# U2FHIDDevice_0.net
KiCad netlist of a schematic drawn in EAGLE
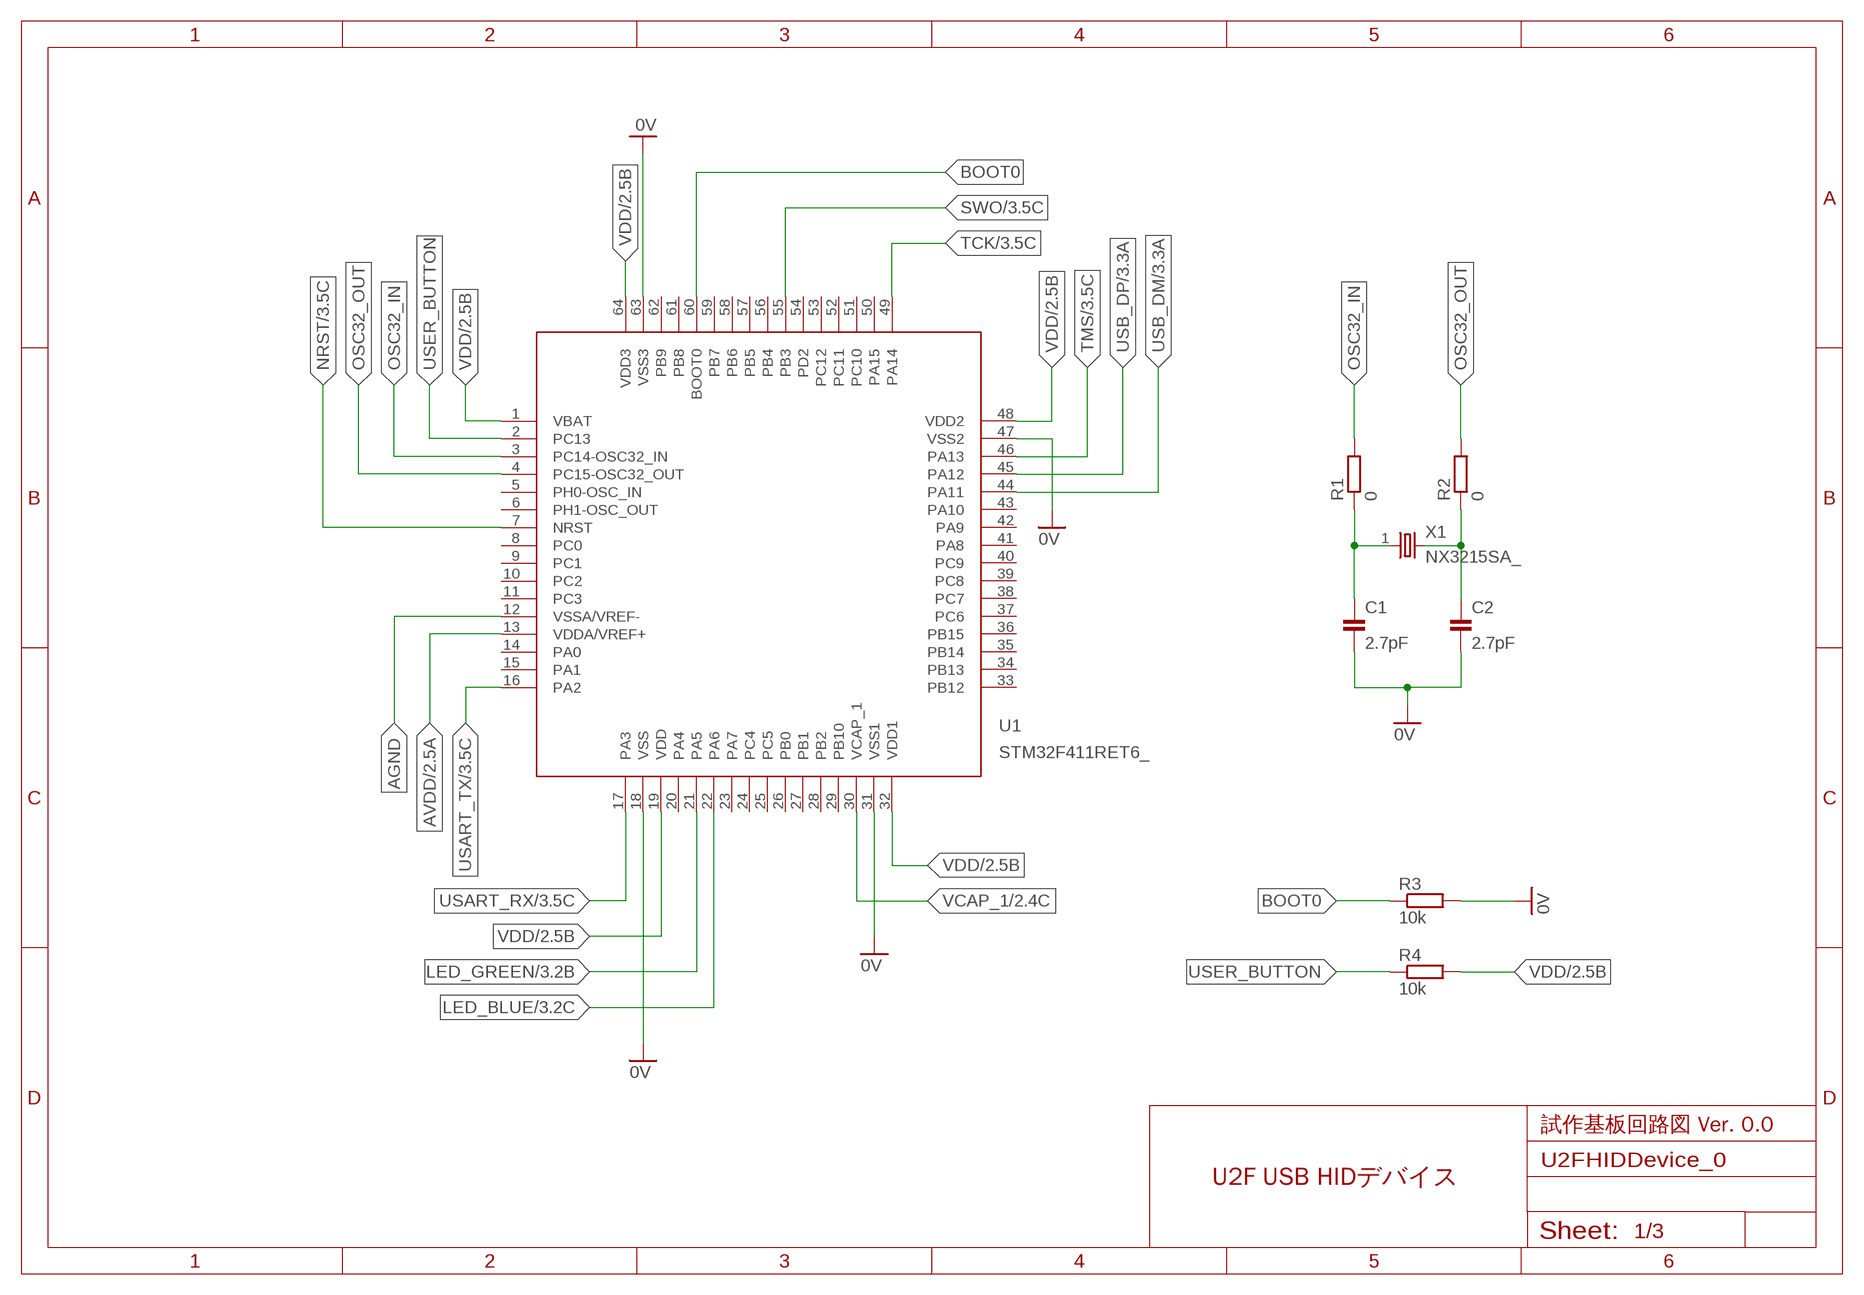
[diagram p0: schematic, sheet 1]
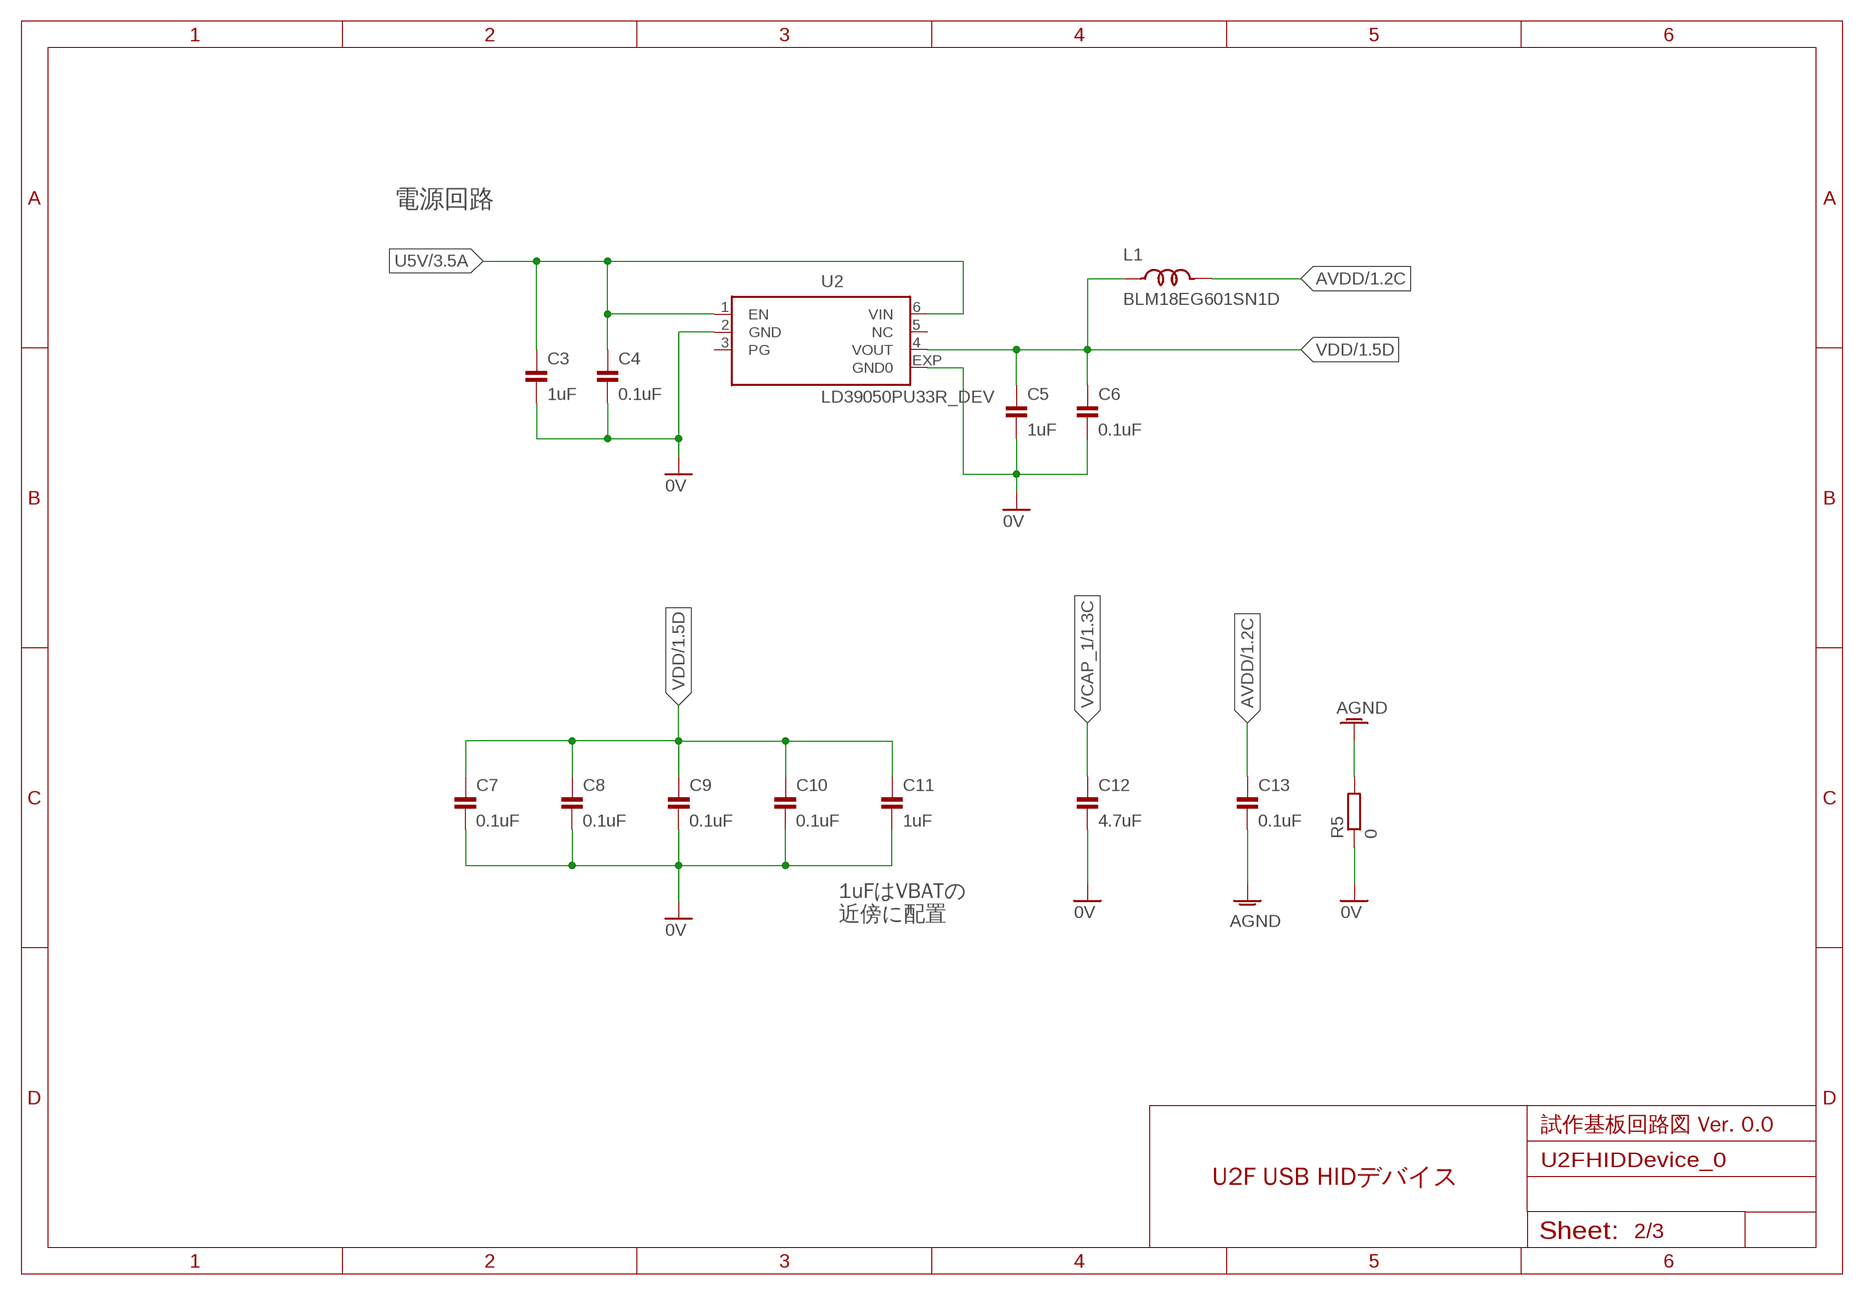
[diagram p1: schematic, sheet 2]
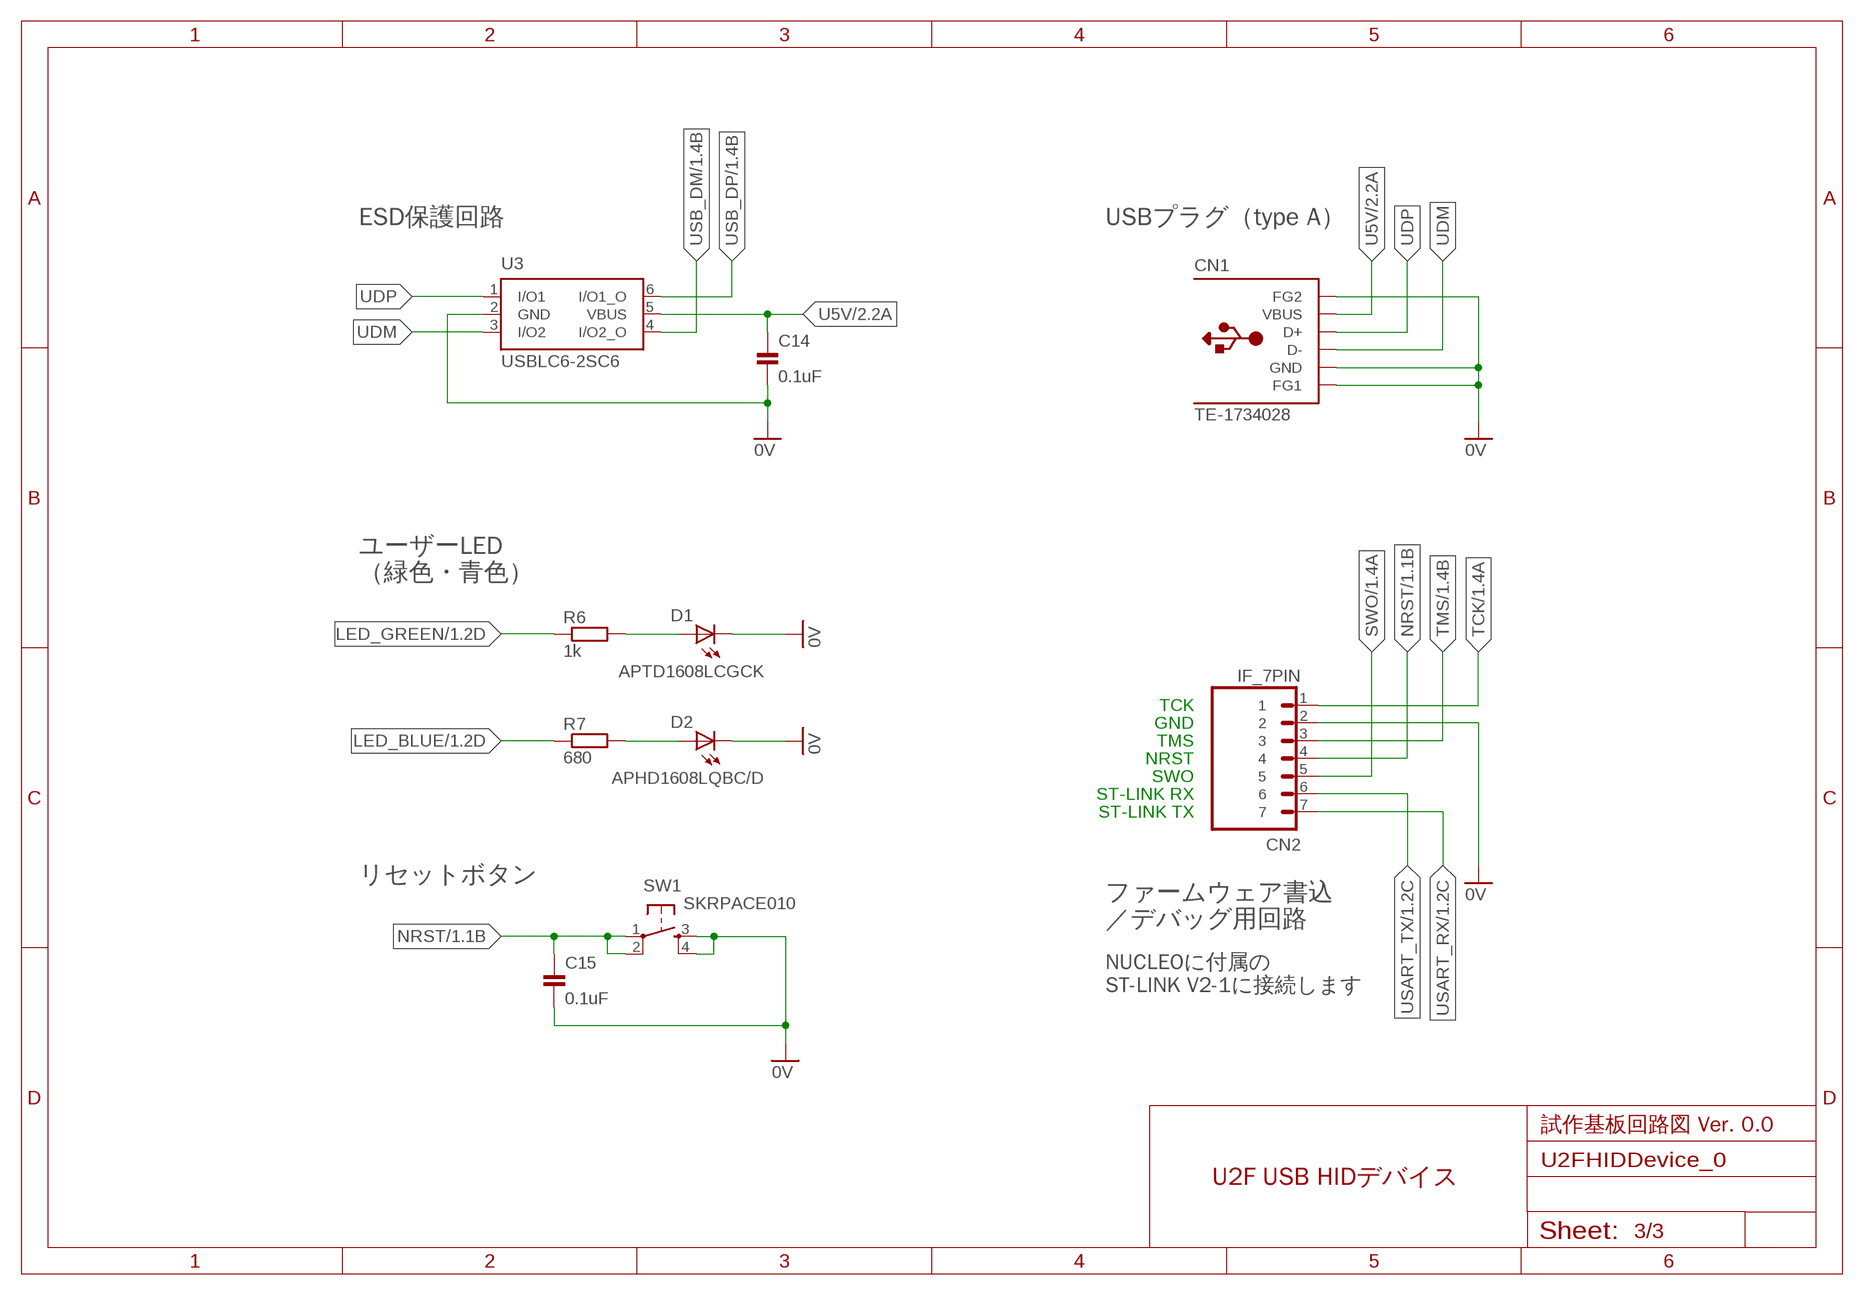
[diagram p2: schematic, sheet 3]

(export (version "E")
  (design (tool "Eeschema 10.0.6"))
  (components
    (comp (ref "C14")
      (value "0.1uF")
      (footprint "eagle-import:C0603K")
      (libsource (lib "eagle-import") (part "CAP_0603"))
    )
    (comp (ref "C15")
      (value "0.1uF")
      (footprint "eagle-import:C0603K")
      (libsource (lib "eagle-import") (part "CAP_0603"))
    )
    (comp (ref "CN1")
      (value "TE-1734028")
      (footprint "eagle-import:TE-1734028")
      (libsource (lib "eagle-import") (part "TE-1734028"))
    )
    (comp (ref "CN2")
      (value "IF_7PIN")
      (footprint "eagle-import:HEADER_7PIN")
      (libsource (lib "eagle-import") (part "IF_7PIN"))
    )
    (comp (ref "D1")
      (value "APTD1608LCGCK")
      (footprint "eagle-import:CHIPLED_0603")
      (libsource (lib "eagle-import") (part "APTD1608LCGCK"))
    )
    (comp (ref "D2")
      (value "APHD1608LQBC/D")
      (footprint "eagle-import:CHIPLED_0603")
      (libsource (lib "eagle-import") (part "APHD1608LQBC/D"))
    )
    (comp (ref "R6")
      (value "1k")
      (footprint "eagle-import:R0603")
      (libsource (lib "eagle-import") (part "RESISTOR_0603"))
    )
    (comp (ref "R7")
      (value "680")
      (footprint "eagle-import:R0603")
      (libsource (lib "eagle-import") (part "RESISTOR_0603"))
    )
    (comp (ref "SW1")
      (value "SKRPACE010")
      (footprint "eagle-import:SKRPACE010")
      (libsource (lib "eagle-import") (part "SKRPACE010"))
    )
    (comp (ref "U3")
      (value "USBLC6-2SC6")
      (footprint "eagle-import:SOT23-6L")
      (libsource (lib "eagle-import") (part "USBLC6-2SC6"))
    )
    (comp (ref "C3")
      (value "1uF")
      (footprint "eagle-import:C0603K")
      (libsource (lib "eagle-import") (part "CAP_0603"))
    )
    (comp (ref "C4")
      (value "0.1uF")
      (footprint "eagle-import:C0603K")
      (libsource (lib "eagle-import") (part "CAP_0603"))
    )
    (comp (ref "C5")
      (value "1uF")
      (footprint "eagle-import:C0603K")
      (libsource (lib "eagle-import") (part "CAP_0603"))
    )
    (comp (ref "C6")
      (value "0.1uF")
      (footprint "eagle-import:C0603K")
      (libsource (lib "eagle-import") (part "CAP_0603"))
    )
    (comp (ref "C7")
      (value "0.1uF")
      (footprint "eagle-import:C0603K")
      (libsource (lib "eagle-import") (part "CAP_0603"))
    )
    (comp (ref "C8")
      (value "0.1uF")
      (footprint "eagle-import:C0603K")
      (libsource (lib "eagle-import") (part "CAP_0603"))
    )
    (comp (ref "C9")
      (value "0.1uF")
      (footprint "eagle-import:C0603K")
      (libsource (lib "eagle-import") (part "CAP_0603"))
    )
    (comp (ref "C10")
      (value "0.1uF")
      (footprint "eagle-import:C0603K")
      (libsource (lib "eagle-import") (part "CAP_0603"))
    )
    (comp (ref "C11")
      (value "1uF")
      (footprint "eagle-import:C0603K")
      (libsource (lib "eagle-import") (part "CAP_0603"))
    )
    (comp (ref "C12")
      (value "4.7uF")
      (footprint "eagle-import:C1206")
      (libsource (lib "eagle-import") (part "CAP_1206"))
    )
    (comp (ref "C13")
      (value "0.1uF")
      (footprint "eagle-import:C0603K")
      (libsource (lib "eagle-import") (part "CAP_0603"))
    )
    (comp (ref "L1")
      (value "BLM18EG601SN1D")
      (footprint "eagle-import:R0603")
      (libsource (lib "eagle-import") (part "BLM18EG601SN1D"))
    )
    (comp (ref "R5")
      (value "0")
      (footprint "eagle-import:R0603")
      (libsource (lib "eagle-import") (part "RESISTOR_0603"))
    )
    (comp (ref "U2")
      (value "LD39050PU33R_DEV")
      (footprint "eagle-import:DFN6-3X3_DEV")
      (libsource (lib "eagle-import") (part "LD39050PU33R_DEV"))
    )
    (comp (ref "C1")
      (value "2.7pF")
      (footprint "eagle-import:C0603K")
      (libsource (lib "eagle-import") (part "CAP_0603"))
    )
    (comp (ref "C2")
      (value "2.7pF")
      (footprint "eagle-import:C0603K")
      (libsource (lib "eagle-import") (part "CAP_0603"))
    )
    (comp (ref "R1")
      (value "0")
      (footprint "eagle-import:R0603")
      (libsource (lib "eagle-import") (part "RESISTOR_0603"))
    )
    (comp (ref "R2")
      (value "0")
      (footprint "eagle-import:R0603")
      (libsource (lib "eagle-import") (part "RESISTOR_0603"))
    )
    (comp (ref "R3")
      (value "10k")
      (footprint "eagle-import:R0603")
      (libsource (lib "eagle-import") (part "RESISTOR_0603"))
    )
    (comp (ref "R4")
      (value "10k")
      (footprint "eagle-import:R0603")
      (libsource (lib "eagle-import") (part "RESISTOR_0603"))
    )
    (comp (ref "U1")
      (value "STM32F411RET6_")
      (footprint "eagle-import:LQFP64-10X10_DEV")
      (libsource (lib "eagle-import") (part "STM32F411RET6_"))
    )
    (comp (ref "X1")
      (value "NX3215SA_")
      (footprint "eagle-import:NX3215_DEV")
      (libsource (lib "eagle-import") (part "NX3215SA_"))
    )
  )
  (nets
    (net (code "1") (name "0V") (class "Default")
      (node (ref "C1") (pin "2") (pinfunction "2_2") (pintype "passive"))
      (node (ref "C10") (pin "2") (pinfunction "2_2") (pintype "passive"))
      (node (ref "C11") (pin "2") (pinfunction "2_2") (pintype "passive"))
      (node (ref "C12") (pin "2") (pinfunction "2_2") (pintype "passive"))
      (node (ref "C14") (pin "2") (pinfunction "2_2") (pintype "passive"))
      (node (ref "C15") (pin "2") (pinfunction "2_2") (pintype "passive"))
      (node (ref "C2") (pin "2") (pinfunction "2_2") (pintype "passive"))
      (node (ref "C3") (pin "2") (pinfunction "2_2") (pintype "passive"))
      (node (ref "C4") (pin "2") (pinfunction "2_2") (pintype "passive"))
      (node (ref "C5") (pin "2") (pinfunction "2_2") (pintype "passive"))
      (node (ref "C6") (pin "2") (pinfunction "2_2") (pintype "passive"))
      (node (ref "C7") (pin "2") (pinfunction "2_2") (pintype "passive"))
      (node (ref "C8") (pin "2") (pinfunction "2_2") (pintype "passive"))
      (node (ref "C9") (pin "2") (pinfunction "2_2") (pintype "passive"))
      (node (ref "CN1") (pin "FG1") (pinfunction "FG1_FG1") (pintype "passive"))
      (node (ref "CN1") (pin "FG2") (pinfunction "FG2_FG2") (pintype "passive"))
      (node (ref "CN1") (pin "P$4") (pinfunction "GND_P$4") (pintype "passive"))
      (node (ref "CN2") (pin "2") (pinfunction "2_2") (pintype "passive"))
      (node (ref "D1") (pin "C") (pinfunction "C_C") (pintype "passive"))
      (node (ref "D2") (pin "C") (pinfunction "C_C") (pintype "passive"))
      (node (ref "R3") (pin "2") (pinfunction "2_2") (pintype "passive"))
      (node (ref "R5") (pin "1") (pinfunction "1_1") (pintype "passive"))
      (node (ref "SW1") (pin "3") (pinfunction "S_3") (pintype "passive"))
      (node (ref "SW1") (pin "4") (pinfunction "S1_4") (pintype "passive"))
      (node (ref "U1") (pin "18") (pinfunction "VSS_18") (pintype "passive"))
      (node (ref "U1") (pin "31") (pinfunction "VSS1_31") (pintype "passive"))
      (node (ref "U1") (pin "47") (pinfunction "VSS2_47") (pintype "passive"))
      (node (ref "U1") (pin "63") (pinfunction "VSS3_63") (pintype "passive"))
      (node (ref "U2") (pin "2") (pinfunction "GND_2") (pintype "passive"))
      (node (ref "U2") (pin "EXP") (pinfunction "GND0_EXP") (pintype "passive"))
      (node (ref "U3") (pin "2") (pinfunction "GND_2") (pintype "passive"))
    )
    (net (code "2") (name "AGND") (class "Default")
      (node (ref "C13") (pin "2") (pinfunction "2_2") (pintype "passive"))
      (node (ref "R5") (pin "2") (pinfunction "2_2") (pintype "passive"))
      (node (ref "U1") (pin "12") (pinfunction "VSSA/VREF-_12") (pintype "passive"))
    )
    (net (code "3") (name "AVDD") (class "Default")
      (node (ref "C13") (pin "1") (pinfunction "1_1") (pintype "passive"))
      (node (ref "L1") (pin "2") (pinfunction "2_2") (pintype "passive"))
      (node (ref "U1") (pin "13") (pinfunction "VDDA/VREF+_13") (pintype "passive"))
    )
    (net (code "4") (name "BOOT0") (class "Default")
      (node (ref "R3") (pin "1") (pinfunction "1_1") (pintype "passive"))
      (node (ref "U1") (pin "60") (pinfunction "BOOT0_60") (pintype "bidirectional"))
    )
    (net (code "5") (name "LED_BLUE") (class "Default")
      (node (ref "R7") (pin "1") (pinfunction "1_1") (pintype "passive"))
      (node (ref "U1") (pin "22") (pinfunction "PA6_22") (pintype "bidirectional"))
    )
    (net (code "6") (name "LED_GREEN") (class "Default")
      (node (ref "R6") (pin "1") (pinfunction "1_1") (pintype "passive"))
      (node (ref "U1") (pin "21") (pinfunction "PA5_21") (pintype "bidirectional"))
    )
    (net (code "7") (name "NRST") (class "Default")
      (node (ref "C15") (pin "1") (pinfunction "1_1") (pintype "passive"))
      (node (ref "CN2") (pin "4") (pinfunction "4_4") (pintype "passive"))
      (node (ref "SW1") (pin "1") (pinfunction "P_1") (pintype "passive"))
      (node (ref "SW1") (pin "2") (pinfunction "P1_2") (pintype "passive"))
      (node (ref "U1") (pin "7") (pinfunction "NRST_7") (pintype "bidirectional"))
    )
    (net (code "8") (name "Net-(C1-Pad1)") (class "Default")
      (node (ref "C1") (pin "1") (pinfunction "1_1") (pintype "passive"))
      (node (ref "R1") (pin "1") (pinfunction "1_1") (pintype "passive"))
      (node (ref "X1") (pin "1") (pinfunction "1_1") (pintype "passive"))
    )
    (net (code "9") (name "Net-(C2-Pad1)") (class "Default")
      (node (ref "C2") (pin "1") (pinfunction "1_1") (pintype "passive"))
      (node (ref "R2") (pin "1") (pinfunction "1_1") (pintype "passive"))
      (node (ref "X1") (pin "2") (pinfunction "2_2") (pintype "passive"))
    )
    (net (code "10") (name "Net-(D1-PadA)") (class "Default")
      (node (ref "D1") (pin "A") (pinfunction "A_A") (pintype "passive"))
      (node (ref "R6") (pin "2") (pinfunction "2_2") (pintype "passive"))
    )
    (net (code "11") (name "Net-(D2-PadA)") (class "Default")
      (node (ref "D2") (pin "A") (pinfunction "A_A") (pintype "passive"))
      (node (ref "R7") (pin "2") (pinfunction "2_2") (pintype "passive"))
    )
    (net (code "12") (name "OSC32_IN") (class "Default")
      (node (ref "R1") (pin "2") (pinfunction "2_2") (pintype "passive"))
      (node (ref "U1") (pin "3") (pinfunction "PC14-OSC32_IN_3") (pintype "bidirectional"))
    )
    (net (code "13") (name "OSC32_OUT") (class "Default")
      (node (ref "R2") (pin "2") (pinfunction "2_2") (pintype "passive"))
      (node (ref "U1") (pin "4") (pinfunction "PC15-OSC32_OUT_4") (pintype "bidirectional"))
    )
    (net (code "14") (name "SWO") (class "Default")
      (node (ref "CN2") (pin "5") (pinfunction "5_5") (pintype "passive"))
      (node (ref "U1") (pin "55") (pinfunction "PB3_55") (pintype "bidirectional"))
    )
    (net (code "15") (name "TCK") (class "Default")
      (node (ref "CN2") (pin "1") (pinfunction "1_1") (pintype "passive"))
      (node (ref "U1") (pin "49") (pinfunction "PA14_49") (pintype "bidirectional"))
    )
    (net (code "16") (name "TMS") (class "Default")
      (node (ref "CN2") (pin "3") (pinfunction "3_3") (pintype "passive"))
      (node (ref "U1") (pin "46") (pinfunction "PA13_46") (pintype "bidirectional"))
    )
    (net (code "17") (name "U5V") (class "Default")
      (node (ref "C14") (pin "1") (pinfunction "1_1") (pintype "passive"))
      (node (ref "C3") (pin "1") (pinfunction "1_1") (pintype "passive"))
      (node (ref "C4") (pin "1") (pinfunction "1_1") (pintype "passive"))
      (node (ref "CN1") (pin "P$1") (pinfunction "VBUS_P$1") (pintype "passive"))
      (node (ref "U2") (pin "1") (pinfunction "EN_1") (pintype "bidirectional"))
      (node (ref "U2") (pin "6") (pinfunction "VIN_6") (pintype "passive"))
      (node (ref "U3") (pin "5") (pinfunction "VBUS_5") (pintype "passive"))
    )
    (net (code "18") (name "UDM") (class "Default")
      (node (ref "CN1") (pin "P$2") (pinfunction "D-_P$2") (pintype "bidirectional"))
      (node (ref "U3") (pin "3") (pinfunction "I/O2_3") (pintype "bidirectional"))
    )
    (net (code "19") (name "UDP") (class "Default")
      (node (ref "CN1") (pin "P$3") (pinfunction "D+_P$3") (pintype "bidirectional"))
      (node (ref "U3") (pin "1") (pinfunction "I/O1_1") (pintype "bidirectional"))
    )
    (net (code "20") (name "USART_RX") (class "Default")
      (node (ref "CN2") (pin "7") (pinfunction "7_7") (pintype "passive"))
      (node (ref "U1") (pin "17") (pinfunction "PA3_17") (pintype "bidirectional"))
    )
    (net (code "21") (name "USART_TX") (class "Default")
      (node (ref "CN2") (pin "6") (pinfunction "6_6") (pintype "passive"))
      (node (ref "U1") (pin "16") (pinfunction "PA2_16") (pintype "bidirectional"))
    )
    (net (code "22") (name "USB_DM") (class "Default")
      (node (ref "U1") (pin "44") (pinfunction "PA11_44") (pintype "bidirectional"))
      (node (ref "U3") (pin "4") (pinfunction "I/O2_O_4") (pintype "bidirectional"))
    )
    (net (code "23") (name "USB_DP") (class "Default")
      (node (ref "U1") (pin "45") (pinfunction "PA12_45") (pintype "bidirectional"))
      (node (ref "U3") (pin "6") (pinfunction "I/O1_O_6") (pintype "bidirectional"))
    )
    (net (code "24") (name "USER_BUTTON") (class "Default")
      (node (ref "R4") (pin "1") (pinfunction "1_1") (pintype "passive"))
      (node (ref "U1") (pin "2") (pinfunction "PC13_2") (pintype "bidirectional"))
    )
    (net (code "25") (name "VCAP_1") (class "Default")
      (node (ref "C12") (pin "1") (pinfunction "1_1") (pintype "passive"))
      (node (ref "U1") (pin "30") (pinfunction "VCAP_1_30") (pintype "passive"))
    )
    (net (code "26") (name "VDD") (class "Default")
      (node (ref "C10") (pin "1") (pinfunction "1_1") (pintype "passive"))
      (node (ref "C11") (pin "1") (pinfunction "1_1") (pintype "passive"))
      (node (ref "C5") (pin "1") (pinfunction "1_1") (pintype "passive"))
      (node (ref "C6") (pin "1") (pinfunction "1_1") (pintype "passive"))
      (node (ref "C7") (pin "1") (pinfunction "1_1") (pintype "passive"))
      (node (ref "C8") (pin "1") (pinfunction "1_1") (pintype "passive"))
      (node (ref "C9") (pin "1") (pinfunction "1_1") (pintype "passive"))
      (node (ref "L1") (pin "1") (pinfunction "1_1") (pintype "passive"))
      (node (ref "R4") (pin "2") (pinfunction "2_2") (pintype "passive"))
      (node (ref "U1") (pin "1") (pinfunction "VBAT_1") (pintype "passive"))
      (node (ref "U1") (pin "19") (pinfunction "VDD_19") (pintype "passive"))
      (node (ref "U1") (pin "32") (pinfunction "VDD1_32") (pintype "passive"))
      (node (ref "U1") (pin "48") (pinfunction "VDD2_48") (pintype "passive"))
      (node (ref "U1") (pin "64") (pinfunction "VDD3_64") (pintype "passive"))
      (node (ref "U2") (pin "4") (pinfunction "VOUT_4") (pintype "passive"))
    )
    (net (code "27") (name "unconnected-(U1-PA0-Pad14)") (class "Default")
      (node (ref "U1") (pin "14") (pinfunction "PA0_14") (pintype "bidirectional"))
    )
    (net (code "28") (name "unconnected-(U1-PA1-Pad15)") (class "Default")
      (node (ref "U1") (pin "15") (pinfunction "PA1_15") (pintype "bidirectional"))
    )
    (net (code "29") (name "unconnected-(U1-PA4-Pad20)") (class "Default")
      (node (ref "U1") (pin "20") (pinfunction "PA4_20") (pintype "bidirectional"))
    )
    (net (code "30") (name "unconnected-(U1-PA7-Pad23)") (class "Default")
      (node (ref "U1") (pin "23") (pinfunction "PA7_23") (pintype "bidirectional"))
    )
    (net (code "31") (name "unconnected-(U1-PA8-Pad41)") (class "Default")
      (node (ref "U1") (pin "41") (pinfunction "PA8_41") (pintype "bidirectional"))
    )
    (net (code "32") (name "unconnected-(U1-PA9-Pad42)") (class "Default")
      (node (ref "U1") (pin "42") (pinfunction "PA9_42") (pintype "bidirectional"))
    )
    (net (code "33") (name "unconnected-(U1-PA10-Pad43)") (class "Default")
      (node (ref "U1") (pin "43") (pinfunction "PA10_43") (pintype "bidirectional"))
    )
    (net (code "34") (name "unconnected-(U1-PA15-Pad50)") (class "Default")
      (node (ref "U1") (pin "50") (pinfunction "PA15_50") (pintype "bidirectional"))
    )
    (net (code "35") (name "unconnected-(U1-PB0-Pad26)") (class "Default")
      (node (ref "U1") (pin "26") (pinfunction "PB0_26") (pintype "bidirectional"))
    )
    (net (code "36") (name "unconnected-(U1-PB1-Pad27)") (class "Default")
      (node (ref "U1") (pin "27") (pinfunction "PB1_27") (pintype "bidirectional"))
    )
    (net (code "37") (name "unconnected-(U1-PB2-Pad28)") (class "Default")
      (node (ref "U1") (pin "28") (pinfunction "PB2_28") (pintype "bidirectional"))
    )
    (net (code "38") (name "unconnected-(U1-PB4-Pad56)") (class "Default")
      (node (ref "U1") (pin "56") (pinfunction "PB4_56") (pintype "bidirectional"))
    )
    (net (code "39") (name "unconnected-(U1-PB5-Pad57)") (class "Default")
      (node (ref "U1") (pin "57") (pinfunction "PB5_57") (pintype "bidirectional"))
    )
    (net (code "40") (name "unconnected-(U1-PB6-Pad58)") (class "Default")
      (node (ref "U1") (pin "58") (pinfunction "PB6_58") (pintype "bidirectional"))
    )
    (net (code "41") (name "unconnected-(U1-PB7-Pad59)") (class "Default")
      (node (ref "U1") (pin "59") (pinfunction "PB7_59") (pintype "bidirectional"))
    )
    (net (code "42") (name "unconnected-(U1-PB8-Pad61)") (class "Default")
      (node (ref "U1") (pin "61") (pinfunction "PB8_61") (pintype "bidirectional"))
    )
    (net (code "43") (name "unconnected-(U1-PB9-Pad62)") (class "Default")
      (node (ref "U1") (pin "62") (pinfunction "PB9_62") (pintype "bidirectional"))
    )
    (net (code "44") (name "unconnected-(U1-PB10-Pad29)") (class "Default")
      (node (ref "U1") (pin "29") (pinfunction "PB10_29") (pintype "bidirectional"))
    )
    (net (code "45") (name "unconnected-(U1-PB12-Pad33)") (class "Default")
      (node (ref "U1") (pin "33") (pinfunction "PB12_33") (pintype "bidirectional"))
    )
    (net (code "46") (name "unconnected-(U1-PB13-Pad34)") (class "Default")
      (node (ref "U1") (pin "34") (pinfunction "PB13_34") (pintype "bidirectional"))
    )
    (net (code "47") (name "unconnected-(U1-PB14-Pad35)") (class "Default")
      (node (ref "U1") (pin "35") (pinfunction "PB14_35") (pintype "bidirectional"))
    )
    (net (code "48") (name "unconnected-(U1-PB15-Pad36)") (class "Default")
      (node (ref "U1") (pin "36") (pinfunction "PB15_36") (pintype "bidirectional"))
    )
    (net (code "49") (name "unconnected-(U1-PC0-Pad8)") (class "Default")
      (node (ref "U1") (pin "8") (pinfunction "PC0_8") (pintype "bidirectional"))
    )
    (net (code "50") (name "unconnected-(U1-PC1-Pad9)") (class "Default")
      (node (ref "U1") (pin "9") (pinfunction "PC1_9") (pintype "bidirectional"))
    )
    (net (code "51") (name "unconnected-(U1-PC2-Pad10)") (class "Default")
      (node (ref "U1") (pin "10") (pinfunction "PC2_10") (pintype "bidirectional"))
    )
    (net (code "52") (name "unconnected-(U1-PC3-Pad11)") (class "Default")
      (node (ref "U1") (pin "11") (pinfunction "PC3_11") (pintype "bidirectional"))
    )
    (net (code "53") (name "unconnected-(U1-PC4-Pad24)") (class "Default")
      (node (ref "U1") (pin "24") (pinfunction "PC4_24") (pintype "bidirectional"))
    )
    (net (code "54") (name "unconnected-(U1-PC5-Pad25)") (class "Default")
      (node (ref "U1") (pin "25") (pinfunction "PC5_25") (pintype "bidirectional"))
    )
    (net (code "55") (name "unconnected-(U1-PC6-Pad37)") (class "Default")
      (node (ref "U1") (pin "37") (pinfunction "PC6_37") (pintype "bidirectional"))
    )
    (net (code "56") (name "unconnected-(U1-PC7-Pad38)") (class "Default")
      (node (ref "U1") (pin "38") (pinfunction "PC7_38") (pintype "bidirectional"))
    )
    (net (code "57") (name "unconnected-(U1-PC8-Pad39)") (class "Default")
      (node (ref "U1") (pin "39") (pinfunction "PC8_39") (pintype "bidirectional"))
    )
    (net (code "58") (name "unconnected-(U1-PC9-Pad40)") (class "Default")
      (node (ref "U1") (pin "40") (pinfunction "PC9_40") (pintype "bidirectional"))
    )
    (net (code "59") (name "unconnected-(U1-PC10-Pad51)") (class "Default")
      (node (ref "U1") (pin "51") (pinfunction "PC10_51") (pintype "bidirectional"))
    )
    (net (code "60") (name "unconnected-(U1-PC11-Pad52)") (class "Default")
      (node (ref "U1") (pin "52") (pinfunction "PC11_52") (pintype "bidirectional"))
    )
    (net (code "61") (name "unconnected-(U1-PC12-Pad53)") (class "Default")
      (node (ref "U1") (pin "53") (pinfunction "PC12_53") (pintype "bidirectional"))
    )
    (net (code "62") (name "unconnected-(U1-PD2-Pad54)") (class "Default")
      (node (ref "U1") (pin "54") (pinfunction "PD2_54") (pintype "bidirectional"))
    )
    (net (code "63") (name "unconnected-(U1-PH0-OSC_IN-Pad5)") (class "Default")
      (node (ref "U1") (pin "5") (pinfunction "PH0-OSC_IN_5") (pintype "bidirectional"))
    )
    (net (code "64") (name "unconnected-(U1-PH1-OSC_OUT-Pad6)") (class "Default")
      (node (ref "U1") (pin "6") (pinfunction "PH1-OSC_OUT_6") (pintype "bidirectional"))
    )
    (net (code "65") (name "unconnected-(U2-NC-Pad5)") (class "Default")
      (node (ref "U2") (pin "5") (pinfunction "NC_5") (pintype "no_connect"))
    )
    (net (code "66") (name "unconnected-(U2-PG-Pad3)") (class "Default")
      (node (ref "U2") (pin "3") (pinfunction "PG_3") (pintype "bidirectional"))
    )
  )
)
